# TCP_2_25.net
KiCad netlist of a schematic drawn in Altium Designer
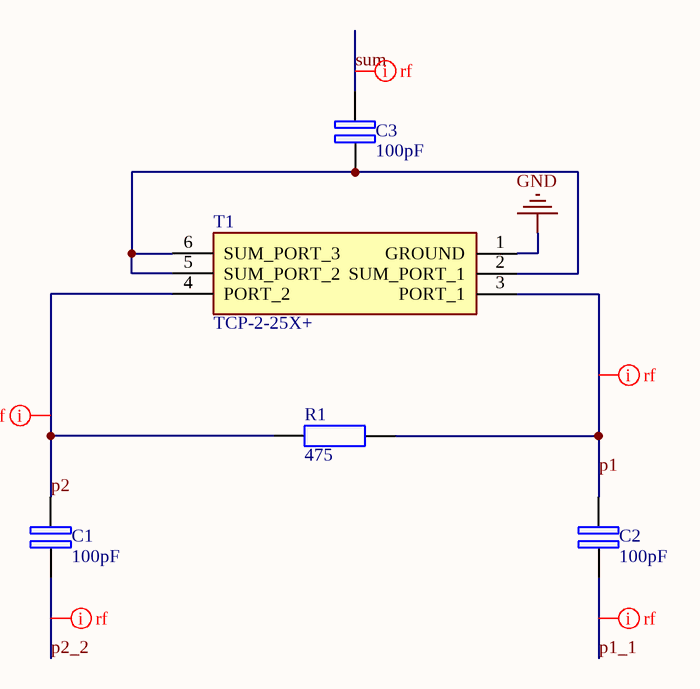
[diagram p0: TCP_2_25.SchDoc]

(export (version "E")
  (design (tool "Eeschema 10.0.6"))
  (components
    (comp (ref "C1")
      (value "100pF")
      (footprint "CAPC0603X08M")
      (description "The capacitor have 2PIN in AXIAL and SMD models.\r\nall non-polar models include.")
      (fields (field (name "CREATOR") "Shahab Azmoodeh") (field (name "CREATED FOR") "HiroNegarPars"))
      (libsource (lib "HiroNegarParsMainLib") (part "Capacitor2P-NP"))
    )
    (comp (ref "C2")
      (value "100pF")
      (footprint "CAPC0603X08M")
      (description "The capacitor have 2PIN in AXIAL and SMD models.\r\nall non-polar models include.")
      (fields (field (name "CREATOR") "Shahab Azmoodeh") (field (name "CREATED FOR") "HiroNegarPars"))
      (libsource (lib "HiroNegarParsMainLib") (part "Capacitor2P-NP"))
    )
    (comp (ref "C3")
      (value "100pF")
      (footprint "CAPC0603X08M")
      (description "The capacitor have 2PIN in AXIAL and SMD models.\r\nall non-polar models include.")
      (fields (field (name "CREATOR") "Shahab Azmoodeh") (field (name "CREATED FOR") "HiroNegarPars"))
      (libsource (lib "HiroNegarParsMainLib") (part "Capacitor2P-NP"))
    )
    (comp (ref "R1")
      (value "475")
      (footprint "RESC0805X05M")
      (description "The resistors have 2PIN in AXIAL and SMD models.\r\nAll wattage include in.")
      (fields (field (name "CREATOR") "Shahab Azmoodeh") (field (name "CREATED FOR") "HiroNegarPars"))
      (libsource (lib "HiroNegarParsMainLib") (part "Resistor2P"))
    )
    (comp (ref "T1")
      (value "TCP-2-25X+")
      (footprint "SamacSys:TCP225X")
      (description "Transformer")
      (fields (field (name "MOUSER PART NUMBER") "139-TCP-2-25X"))
      (libsource (lib "*") (part "TCP-2-25X+"))
    )
  )
  (nets
    (net (code "1") (name "/p1") (class "Default")
      (node (ref "C2") (pin "2") (pinfunction "2_2") (pintype "passive"))
      (node (ref "R1") (pin "1") (pinfunction "1_1") (pintype "passive"))
      (node (ref "T1") (pin "3") (pinfunction "PORT_1_3") (pintype "passive"))
    )
    (net (code "2") (name "/p1_1") (class "Default")
      (node (ref "C2") (pin "1") (pinfunction "1_1") (pintype "passive"))
    )
    (net (code "3") (name "/p2") (class "Default")
      (node (ref "C1") (pin "2") (pinfunction "2_2") (pintype "passive"))
      (node (ref "R1") (pin "2") (pinfunction "2_2") (pintype "passive"))
      (node (ref "T1") (pin "4") (pinfunction "PORT_2_4") (pintype "passive"))
    )
    (net (code "4") (name "/p2_2") (class "Default")
      (node (ref "C1") (pin "1") (pinfunction "1_1") (pintype "passive"))
    )
    (net (code "5") (name "/sum") (class "Default")
      (node (ref "C3") (pin "2") (pinfunction "2_2") (pintype "passive"))
    )
    (net (code "6") (name "GND") (class "Default")
      (node (ref "T1") (pin "1") (pinfunction "GROUND_1") (pintype "passive"))
    )
    (net (code "7") (name "Net-(T1-SUM_PORT_1)") (class "Default")
      (node (ref "C3") (pin "1") (pinfunction "1_1") (pintype "passive"))
      (node (ref "T1") (pin "2") (pinfunction "SUM_PORT_1_2") (pintype "passive"))
      (node (ref "T1") (pin "5") (pinfunction "SUM_PORT_2_5") (pintype "passive"))
      (node (ref "T1") (pin "6") (pinfunction "SUM_PORT_3_6") (pintype "passive"))
    )
  )
)
